# 0_3cbrd.net
KiCad netlist of a schematic drawn in EAGLE
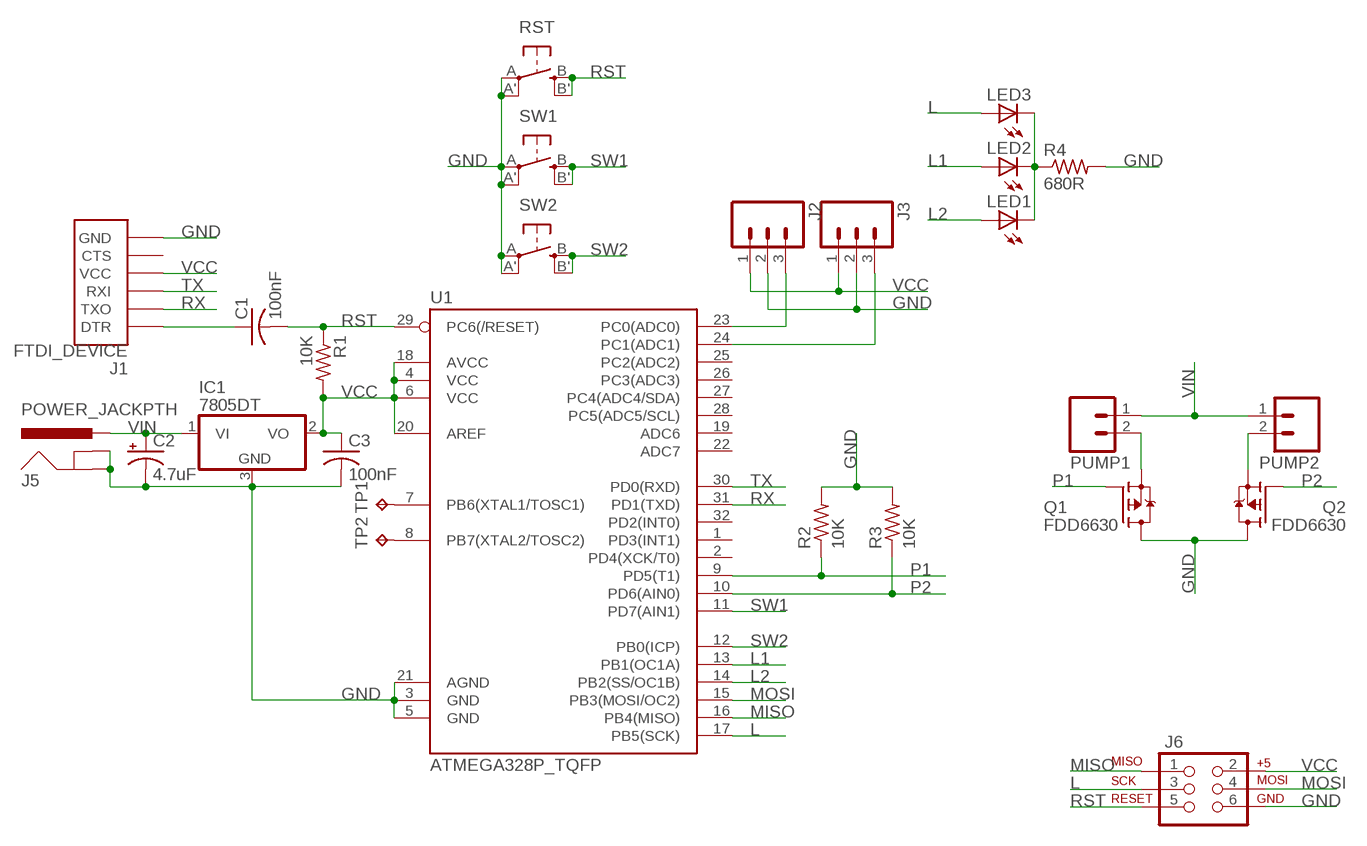
[diagram p0: schematic, sheet 1]

(export (version "E")
  (design (tool "Eeschema 10.0.6"))
  (components
    (comp (ref "C1")
      (value "100nF")
      (footprint "eagle-import:C1206K")
      (libsource (lib "eagle-import") (part "resistor_C-USC1206K"))
    )
    (comp (ref "C2")
      (value "4.7uF")
      (footprint "eagle-import:153CLV-0405")
      (libsource (lib "eagle-import") (part "CPOL-US153CLV-0405"))
    )
    (comp (ref "C3")
      (value "100nF")
      (footprint "eagle-import:C1206K")
      (libsource (lib "eagle-import") (part "C-USC1206K"))
    )
    (comp (ref "IC1")
      (value "7805DT")
      (footprint "eagle-import:TO252")
      (libsource (lib "eagle-import") (part "78DT05"))
    )
    (comp (ref "J1")
      (value "FTDI_DEVICE")
      (footprint "eagle-import:FTDI_DEVICE_SIDE")
      (libsource (lib "eagle-import") (part "FTDI_DEVICE"))
    )
    (comp (ref "J2")
      (value "M03PTH")
      (footprint "eagle-import:1X03")
      (libsource (lib "eagle-import") (part "M03PTH"))
    )
    (comp (ref "J3")
      (value "M03PTH")
      (footprint "eagle-import:1X03")
      (libsource (lib "eagle-import") (part "M03PTH"))
    )
    (comp (ref "J5")
      (value "POWER_JACKPTH")
      (footprint "eagle-import:POWER_JACK_PTH")
      (libsource (lib "eagle-import") (part "POWER_JACKPTH"))
    )
    (comp (ref "J6")
      (value "AVR_SPI_PRG_6PTH")
      (footprint "eagle-import:2X3")
      (libsource (lib "eagle-import") (part "AVR_SPI_PRG_6PTH"))
    )
    (comp (ref "LED1")
      (value "LED3MM")
      (footprint "eagle-import:LED3MM")
      (libsource (lib "eagle-import") (part "LED3MM"))
    )
    (comp (ref "LED2")
      (value "LED3MM")
      (footprint "eagle-import:LED3MM")
      (libsource (lib "eagle-import") (part "LED3MM"))
    )
    (comp (ref "LED3")
      (value "LED3MM")
      (footprint "eagle-import:LED3MM")
      (libsource (lib "eagle-import") (part "LED3MM"))
    )
    (comp (ref "PUMP1")
      (value "M02PTH")
      (footprint "eagle-import:1X02")
      (libsource (lib "eagle-import") (part "M02PTH"))
    )
    (comp (ref "PUMP2")
      (value "M02PTH")
      (footprint "eagle-import:1X02")
      (libsource (lib "eagle-import") (part "M02PTH"))
    )
    (comp (ref "Q1")
      (value "FDD6630")
      (footprint "eagle-import:TO252")
      (libsource (lib "eagle-import") (part "FDD4141TO252"))
    )
    (comp (ref "Q2")
      (value "FDD6630")
      (footprint "eagle-import:TO252")
      (libsource (lib "eagle-import") (part "FDD4141TO252"))
    )
    (comp (ref "R1")
      (value "10K")
      (footprint "eagle-import:M0805")
      (libsource (lib "eagle-import") (part "R-US_M0805"))
    )
    (comp (ref "R2")
      (value "10K")
      (footprint "eagle-import:M0805")
      (libsource (lib "eagle-import") (part "R-US_M0805"))
    )
    (comp (ref "R3")
      (value "10K")
      (footprint "eagle-import:M0805")
      (libsource (lib "eagle-import") (part "R-US_M0805"))
    )
    (comp (ref "R4")
      (value "680R")
      (footprint "eagle-import:M0805")
      (libsource (lib "eagle-import") (part "R-US_M0805"))
    )
    (comp (ref "RST")
      (value "SPST_TACT-EVQQ2")
      (footprint "eagle-import:EVQ-Q2")
      (libsource (lib "eagle-import") (part "SPST_TACT-EVQQ2"))
    )
    (comp (ref "SW1")
      (value "SPST_TACT-EVQQ2")
      (footprint "eagle-import:EVQ-Q2")
      (libsource (lib "eagle-import") (part "SPST_TACT-EVQQ2"))
    )
    (comp (ref "SW2")
      (value "SPST_TACT-EVQQ2")
      (footprint "eagle-import:EVQ-Q2")
      (libsource (lib "eagle-import") (part "SPST_TACT-EVQQ2"))
    )
    (comp (ref "TP1")
      (value "TPTP15SQ")
      (footprint "eagle-import:TP15SQ")
      (libsource (lib "eagle-import") (part "TPTP15SQ"))
    )
    (comp (ref "TP2")
      (value "TPTP15SQ")
      (footprint "eagle-import:TP15SQ")
      (libsource (lib "eagle-import") (part "TPTP15SQ"))
    )
    (comp (ref "U1")
      (value "ATMEGA328P_TQFP")
      (footprint "eagle-import:TQFP32-08")
      (libsource (lib "eagle-import") (part "ATMEGA328P_TQFP"))
    )
  )
  (nets
    (net (code "1") (name "/GND") (class "Default")
      (node (ref "C2") (pin "-") (pinfunction "-_-") (pintype "passive"))
      (node (ref "C3") (pin "2") (pinfunction "2_2") (pintype "passive"))
      (node (ref "IC1") (pin "3") (pinfunction "GND_3") (pintype "passive"))
      (node (ref "J1") (pin "P$6") (pinfunction "GND_P$6") (pintype "bidirectional"))
      (node (ref "J2") (pin "2") (pinfunction "2_2") (pintype "passive"))
      (node (ref "J3") (pin "2") (pinfunction "2_2") (pintype "passive"))
      (node (ref "J5") (pin "GND") (pinfunction "GND_GND") (pintype "bidirectional"))
      (node (ref "J5") (pin "GNDBREAK") (pinfunction "GNDBREAK_GNDBREAK") (pintype "bidirectional"))
      (node (ref "J6") (pin "6") (pinfunction "6_6") (pintype "passive"))
      (node (ref "Q1") (pin "3") (pinfunction "D_3") (pintype "passive"))
      (node (ref "Q2") (pin "3") (pinfunction "D_3") (pintype "passive"))
      (node (ref "R2") (pin "2") (pinfunction "2_2") (pintype "passive"))
      (node (ref "R3") (pin "2") (pinfunction "2_2") (pintype "passive"))
      (node (ref "R4") (pin "2") (pinfunction "2_2") (pintype "passive"))
      (node (ref "RST") (pin "A") (pinfunction "P_A") (pintype "passive"))
      (node (ref "RST") (pin "A'") (pinfunction "P1_A'") (pintype "passive"))
      (node (ref "SW1") (pin "A") (pinfunction "P_A") (pintype "passive"))
      (node (ref "SW1") (pin "A'") (pinfunction "P1_A'") (pintype "passive"))
      (node (ref "SW2") (pin "A") (pinfunction "P_A") (pintype "passive"))
      (node (ref "SW2") (pin "A'") (pinfunction "P1_A'") (pintype "passive"))
      (node (ref "U1") (pin "21") (pinfunction "AGND_21") (pintype "bidirectional"))
      (node (ref "U1") (pin "3") (pinfunction "GND_3") (pintype "bidirectional"))
      (node (ref "U1") (pin "5") (pinfunction "GND_5") (pintype "bidirectional"))
    )
    (net (code "2") (name "/L") (class "Default")
      (node (ref "J6") (pin "3") (pinfunction "3_3") (pintype "passive"))
      (node (ref "LED3") (pin "A") (pinfunction "A_A") (pintype "passive"))
      (node (ref "U1") (pin "17") (pinfunction "PB5(SCK)_17") (pintype "bidirectional"))
    )
    (net (code "3") (name "/L1") (class "Default")
      (node (ref "LED2") (pin "A") (pinfunction "A_A") (pintype "passive"))
      (node (ref "U1") (pin "13") (pinfunction "PB1(OC1A)_13") (pintype "bidirectional"))
    )
    (net (code "4") (name "/L2") (class "Default")
      (node (ref "LED1") (pin "A") (pinfunction "A_A") (pintype "passive"))
      (node (ref "U1") (pin "14") (pinfunction "PB2(SS/OC1B)_14") (pintype "bidirectional"))
    )
    (net (code "5") (name "/MISO") (class "Default")
      (node (ref "J6") (pin "1") (pinfunction "1_1") (pintype "passive"))
      (node (ref "U1") (pin "16") (pinfunction "PB4(MISO)_16") (pintype "bidirectional"))
    )
    (net (code "6") (name "/MOSI") (class "Default")
      (node (ref "J6") (pin "4") (pinfunction "4_4") (pintype "passive"))
      (node (ref "U1") (pin "15") (pinfunction "PB3(MOSI/OC2)_15") (pintype "bidirectional"))
    )
    (net (code "7") (name "/P1") (class "Default")
      (node (ref "Q1") (pin "1") (pinfunction "G_1") (pintype "passive"))
      (node (ref "R2") (pin "1") (pinfunction "1_1") (pintype "passive"))
      (node (ref "U1") (pin "9") (pinfunction "PD5(T1)_9") (pintype "bidirectional"))
    )
    (net (code "8") (name "/P2") (class "Default")
      (node (ref "Q2") (pin "1") (pinfunction "G_1") (pintype "passive"))
      (node (ref "R3") (pin "1") (pinfunction "1_1") (pintype "passive"))
      (node (ref "U1") (pin "10") (pinfunction "PD6(AIN0)_10") (pintype "bidirectional"))
    )
    (net (code "9") (name "/RST") (class "Default")
      (node (ref "C1") (pin "2") (pinfunction "2_2") (pintype "passive"))
      (node (ref "J6") (pin "5") (pinfunction "5_5") (pintype "passive"))
      (node (ref "R1") (pin "1") (pinfunction "1_1") (pintype "passive"))
      (node (ref "RST") (pin "B") (pinfunction "S_B") (pintype "passive"))
      (node (ref "RST") (pin "B'") (pinfunction "S1_B'") (pintype "passive"))
      (node (ref "U1") (pin "29") (pinfunction "PC6(/RESET)_29") (pintype "bidirectional"))
    )
    (net (code "10") (name "/RX") (class "Default")
      (node (ref "J1") (pin "P$2") (pinfunction "TXO_P$2") (pintype "bidirectional"))
      (node (ref "U1") (pin "31") (pinfunction "PD1(TXD)_31") (pintype "bidirectional"))
    )
    (net (code "11") (name "/SW1") (class "Default")
      (node (ref "SW1") (pin "B") (pinfunction "S_B") (pintype "passive"))
      (node (ref "SW1") (pin "B'") (pinfunction "S1_B'") (pintype "passive"))
      (node (ref "U1") (pin "11") (pinfunction "PD7(AIN1)_11") (pintype "bidirectional"))
    )
    (net (code "12") (name "/SW2") (class "Default")
      (node (ref "SW2") (pin "B") (pinfunction "S_B") (pintype "passive"))
      (node (ref "SW2") (pin "B'") (pinfunction "S1_B'") (pintype "passive"))
      (node (ref "U1") (pin "12") (pinfunction "PB0(ICP)_12") (pintype "bidirectional"))
    )
    (net (code "13") (name "/TX") (class "Default")
      (node (ref "J1") (pin "P$3") (pinfunction "RXI_P$3") (pintype "bidirectional"))
      (node (ref "U1") (pin "30") (pinfunction "PD0(RXD)_30") (pintype "bidirectional"))
    )
    (net (code "14") (name "/VCC") (class "Default")
      (node (ref "C3") (pin "1") (pinfunction "1_1") (pintype "passive"))
      (node (ref "IC1") (pin "2") (pinfunction "VO_2") (pintype "passive"))
      (node (ref "J1") (pin "P$4") (pinfunction "VCC_P$4") (pintype "bidirectional"))
      (node (ref "J2") (pin "1") (pinfunction "1_1") (pintype "passive"))
      (node (ref "J3") (pin "1") (pinfunction "1_1") (pintype "passive"))
      (node (ref "J6") (pin "2") (pinfunction "2_2") (pintype "passive"))
      (node (ref "R1") (pin "2") (pinfunction "2_2") (pintype "passive"))
      (node (ref "U1") (pin "18") (pinfunction "AVCC_18") (pintype "bidirectional"))
      (node (ref "U1") (pin "20") (pinfunction "AREF_20") (pintype "bidirectional"))
      (node (ref "U1") (pin "4") (pinfunction "VCC_4") (pintype "bidirectional"))
      (node (ref "U1") (pin "6") (pinfunction "VCC_6") (pintype "bidirectional"))
    )
    (net (code "15") (name "/VIN") (class "Default")
      (node (ref "C2") (pin "+") (pinfunction "+_+") (pintype "passive"))
      (node (ref "IC1") (pin "1") (pinfunction "VI_1") (pintype "input"))
      (node (ref "J5") (pin "PWR") (pinfunction "PWR_PWR") (pintype "bidirectional"))
      (node (ref "PUMP1") (pin "1") (pinfunction "1_1") (pintype "passive"))
      (node (ref "PUMP2") (pin "1") (pinfunction "1_1") (pintype "passive"))
    )
    (net (code "16") (name "Net-(J1-DTR)") (class "Default")
      (node (ref "C1") (pin "1") (pinfunction "1_1") (pintype "passive"))
      (node (ref "J1") (pin "P$1") (pinfunction "DTR_P$1") (pintype "bidirectional"))
    )
    (net (code "17") (name "Net-(LED1-C)") (class "Default")
      (node (ref "LED1") (pin "K") (pinfunction "C_K") (pintype "passive"))
      (node (ref "LED2") (pin "K") (pinfunction "C_K") (pintype "passive"))
      (node (ref "LED3") (pin "K") (pinfunction "C_K") (pintype "passive"))
      (node (ref "R4") (pin "1") (pinfunction "1_1") (pintype "passive"))
    )
    (net (code "18") (name "Net-(Q1-S)") (class "Default")
      (node (ref "PUMP1") (pin "2") (pinfunction "2_2") (pintype "passive"))
      (node (ref "Q1") (pin "2") (pinfunction "S_2") (pintype "passive"))
    )
    (net (code "19") (name "Net-(Q2-S)") (class "Default")
      (node (ref "PUMP2") (pin "2") (pinfunction "2_2") (pintype "passive"))
      (node (ref "Q2") (pin "2") (pinfunction "S_2") (pintype "passive"))
    )
    (net (code "20") (name "Net-(U1-PB6(XTAL1{slash}TOSC1))") (class "Default")
      (node (ref "TP1") (pin "TP") (pinfunction "TP_TP") (pintype "input"))
      (node (ref "U1") (pin "7") (pinfunction "PB6(XTAL1/TOSC1)_7") (pintype "bidirectional"))
    )
    (net (code "21") (name "Net-(U1-PB7(XTAL2{slash}TOSC2))") (class "Default")
      (node (ref "TP2") (pin "TP") (pinfunction "TP_TP") (pintype "input"))
      (node (ref "U1") (pin "8") (pinfunction "PB7(XTAL2/TOSC2)_8") (pintype "bidirectional"))
    )
    (net (code "22") (name "Net-(U1-PC0(ADC0))") (class "Default")
      (node (ref "J2") (pin "3") (pinfunction "3_3") (pintype "passive"))
      (node (ref "U1") (pin "23") (pinfunction "PC0(ADC0)_23") (pintype "bidirectional"))
    )
    (net (code "23") (name "Net-(U1-PC1(ADC1))") (class "Default")
      (node (ref "J3") (pin "3") (pinfunction "3_3") (pintype "passive"))
      (node (ref "U1") (pin "24") (pinfunction "PC1(ADC1)_24") (pintype "bidirectional"))
    )
    (net (code "24") (name "unconnected-(J1-CTS-PadP$5)") (class "Default")
      (node (ref "J1") (pin "P$5") (pinfunction "CTS_P$5") (pintype "bidirectional"))
    )
    (net (code "25") (name "unconnected-(U1-ADC6-Pad19)") (class "Default")
      (node (ref "U1") (pin "19") (pinfunction "ADC6_19") (pintype "bidirectional"))
    )
    (net (code "26") (name "unconnected-(U1-ADC7-Pad22)") (class "Default")
      (node (ref "U1") (pin "22") (pinfunction "ADC7_22") (pintype "bidirectional"))
    )
    (net (code "27") (name "unconnected-(U1-PC2(ADC2)-Pad25)") (class "Default")
      (node (ref "U1") (pin "25") (pinfunction "PC2(ADC2)_25") (pintype "bidirectional"))
    )
    (net (code "28") (name "unconnected-(U1-PC3(ADC3)-Pad26)") (class "Default")
      (node (ref "U1") (pin "26") (pinfunction "PC3(ADC3)_26") (pintype "bidirectional"))
    )
    (net (code "29") (name "unconnected-(U1-PC4(ADC4{slash}SDA)-Pad27)") (class "Default")
      (node (ref "U1") (pin "27") (pinfunction "PC4(ADC4/SDA)_27") (pintype "bidirectional"))
    )
    (net (code "30") (name "unconnected-(U1-PC5(ADC5{slash}SCL)-Pad28)") (class "Default")
      (node (ref "U1") (pin "28") (pinfunction "PC5(ADC5/SCL)_28") (pintype "bidirectional"))
    )
    (net (code "31") (name "unconnected-(U1-PD2(INT0)-Pad32)") (class "Default")
      (node (ref "U1") (pin "32") (pinfunction "PD2(INT0)_32") (pintype "bidirectional"))
    )
    (net (code "32") (name "unconnected-(U1-PD3(INT1)-Pad1)") (class "Default")
      (node (ref "U1") (pin "1") (pinfunction "PD3(INT1)_1") (pintype "bidirectional"))
    )
    (net (code "33") (name "unconnected-(U1-PD4(XCK{slash}T0)-Pad2)") (class "Default")
      (node (ref "U1") (pin "2") (pinfunction "PD4(XCK/T0)_2") (pintype "bidirectional"))
    )
  )
)
